# Thermocouple.net
KiCad netlist of a schematic drawn in Altium Designer
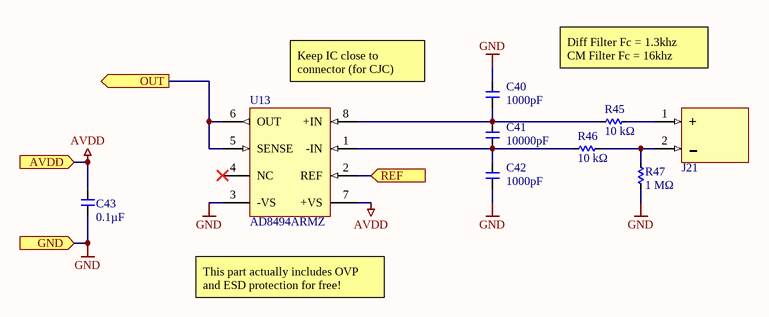
[diagram p0: Thermocouple.SchDoc]

(export (version "E")
  (design (tool "Eeschema 10.0.6"))
  (components
    (comp (ref "C40")
      (value "490-1494-1-ND")
      (footprint "C0603")
      (description "CAP CER 0603 1000pF X7R 50V 10%")
      (fields
        (field (name "MANUFACTURER") "Murata Electronics North America")
        (field (name "CAPACITANCE (SHORTHAND)") "1000pF")
      )
      (libsource (lib "Stanford Student Space Initiative") (part "__template_cap"))
    )
    (comp (ref "C41")
      (value "490-1512-1-ND")
      (footprint "C0603")
      (description "CAP CER 0603 10000pF X7R 50V 10%")
      (fields
        (field (name "MANUFACTURER") "Murata Electronics North America")
        (field (name "CAPACITANCE (SHORTHAND)") "10000pF")
      )
      (libsource (lib "Stanford Student Space Initiative") (part "__template_cap"))
    )
    (comp (ref "C42")
      (value "490-1494-1-ND")
      (footprint "C0603")
      (description "CAP CER 0603 1000pF X7R 50V 10%")
      (fields
        (field (name "MANUFACTURER") "Murata Electronics North America")
        (field (name "CAPACITANCE (SHORTHAND)") "1000pF")
      )
      (libsource (lib "Stanford Student Space Initiative") (part "__template_cap"))
    )
    (comp (ref "C43")
      (value "490-1519-1-ND")
      (footprint "C0603")
      (description "CAP CER 0603 0.1µF X7R 50V 10%")
      (fields
        (field (name "MANUFACTURER") "Murata Electronics North America")
        (field (name "CAPACITANCE (SHORTHAND)") "0.1µF")
      )
      (libsource (lib "Stanford Student Space Initiative") (part "__template_cap"))
    )
    (comp (ref "J21")
      (value "PCC-SMP-V-K")
      (footprint "PCC-SMP-V-K-Footprint-1")
      (libsource (lib "Stanford Student Space Initiative") (part "PCC-SMP-V-K"))
    )
    (comp (ref "R45")
      (value "311-10.0KHRCT-ND")
      (footprint "R0603")
      (description "RES SMD 10K OHM 1% 1/10W 0603")
      (fields
        (field (name "TOLERANCE") "±1%")
        (field (name "MANUFACTURER PART NUMBER") "RC0603FR-0710KL")
        (field (name "RESISTANCE") "10 kΩ")
      )
      (libsource (lib "Stanford Student Space Initiative") (part "__template_resistor"))
    )
    (comp (ref "R46")
      (value "311-10.0KHRCT-ND")
      (footprint "R0603")
      (description "RES SMD 10K OHM 1% 1/10W 0603")
      (fields
        (field (name "TOLERANCE") "±1%")
        (field (name "MANUFACTURER PART NUMBER") "RC0603FR-0710KL")
        (field (name "RESISTANCE") "10 kΩ")
      )
      (libsource (lib "Stanford Student Space Initiative") (part "__template_resistor"))
    )
    (comp (ref "R47")
      (value "311-1.00MHRCT-ND")
      (footprint "R0603")
      (description "RES SMD 1M OHM 1% 1/10W 0603")
      (fields
        (field (name "MANUFACTURER PART NUMBER") "RC0603FR-071ML")
        (field (name "RESISTANCE") "1 MΩ")
        (field (name "MANUFACTURER") "Yageo")
      )
      (libsource (lib "Stanford Student Space Initiative") (part "__template_resistor"))
    )
    (comp (ref "U13")
      (value "AD8494ARMZ")
      (footprint "ADI-RM-8_N")
      (description "IC THRMOCPLE COLD JNC COMP 8MSOP")
      (libsource (lib "Stanford Student Space Initiative") (part "ADI-AD849X-RM-8"))
    )
  )
  (nets
    (net (code "1") (name "/OUT") (class "Default")
      (node (ref "U13") (pin "5") (pinfunction "SENSE_5") (pintype "input"))
      (node (ref "U13") (pin "6") (pinfunction "OUT_6") (pintype "output"))
    )
    (net (code "2") (name "/REF") (class "Default")
      (node (ref "U13") (pin "2") (pinfunction "REF_2") (pintype "input"))
    )
    (net (code "3") (name "AVDD") (class "Default")
      (node (ref "C43") (pin "1") (pintype "passive"))
      (node (ref "U13") (pin "7") (pinfunction "+VS_7") (pintype "power_in"))
    )
    (net (code "4") (name "GND") (class "Default")
      (node (ref "C40") (pin "1") (pintype "passive"))
      (node (ref "C42") (pin "2") (pintype "passive"))
      (node (ref "C43") (pin "2") (pintype "passive"))
      (node (ref "R47") (pin "1") (pinfunction "1_1") (pintype "passive"))
      (node (ref "U13") (pin "3") (pinfunction "-VS_3") (pintype "power_in"))
    )
    (net (code "5") (name "Net-(J21-+)") (class "Default")
      (node (ref "J21") (pin "1") (pinfunction "+_1") (pintype "input"))
      (node (ref "R45") (pin "2") (pinfunction "2_2") (pintype "passive"))
    )
    (net (code "6") (name "Net-(J21--)") (class "Default")
      (node (ref "J21") (pin "2") (pinfunction "-_2") (pintype "input"))
      (node (ref "R46") (pin "2") (pinfunction "2_2") (pintype "passive"))
      (node (ref "R47") (pin "2") (pinfunction "2_2") (pintype "passive"))
    )
    (net (code "7") (name "Net-(U13-+IN)") (class "Default")
      (node (ref "C40") (pin "2") (pintype "passive"))
      (node (ref "C41") (pin "1") (pintype "passive"))
      (node (ref "R45") (pin "1") (pinfunction "1_1") (pintype "passive"))
      (node (ref "U13") (pin "8") (pinfunction "+IN_8") (pintype "input"))
    )
    (net (code "8") (name "Net-(U13--IN)") (class "Default")
      (node (ref "C41") (pin "2") (pintype "passive"))
      (node (ref "C42") (pin "1") (pintype "passive"))
      (node (ref "R46") (pin "1") (pinfunction "1_1") (pintype "passive"))
      (node (ref "U13") (pin "1") (pinfunction "-IN_1") (pintype "input"))
    )
    (net (code "9") (name "unconnected-(U13-NC-Pad4)") (class "Default")
      (node (ref "U13") (pin "4") (pinfunction "NC_4") (pintype "passive+no_connect"))
    )
  )
)
